# EstopperSchema.net
KiCad netlist of a schematic drawn in EAGLE
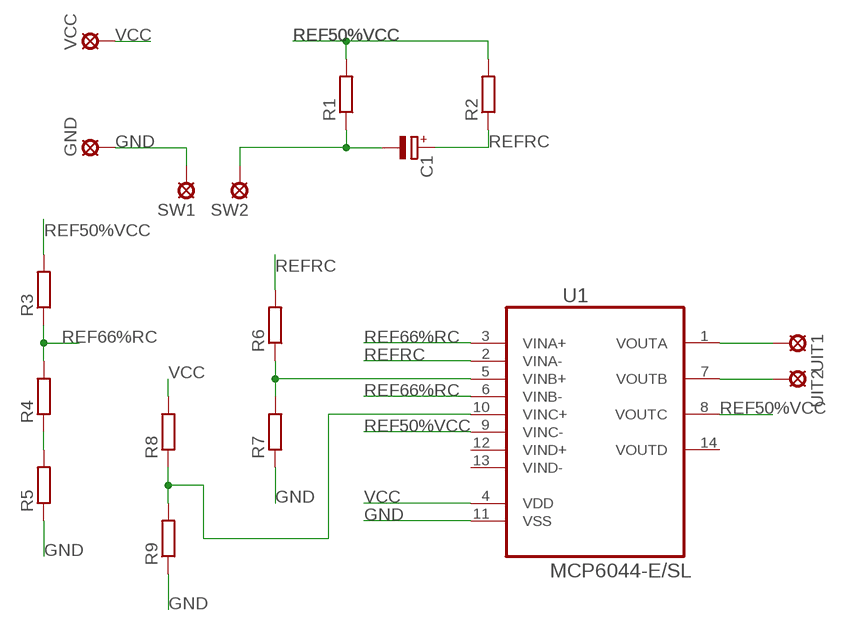
[diagram p0: schematic, sheet 1]

(export (version "E")
  (design (tool "Eeschema 10.0.6"))
  (components
    (comp (ref "C1")
      (value "CPOL-EU140CLH-0810")
      (footprint "eagle-import:140CLH-0810")
      (libsource (lib "eagle-import") (part "CPOL-EU140CLH-0810"))
    )
    (comp (ref "GND")
      (value "LSP11")
      (footprint "eagle-import:LSP11")
      (libsource (lib "eagle-import") (part "LSP11"))
    )
    (comp (ref "R1")
      (value "R-EU_M1206")
      (footprint "eagle-import:M1206")
      (libsource (lib "eagle-import") (part "R-EU_M1206"))
    )
    (comp (ref "R2")
      (value "R-EU_M1206")
      (footprint "eagle-import:M1206")
      (libsource (lib "eagle-import") (part "R-EU_M1206"))
    )
    (comp (ref "R3")
      (value "R-EU_M1206")
      (footprint "eagle-import:M1206")
      (libsource (lib "eagle-import") (part "R-EU_M1206"))
    )
    (comp (ref "R4")
      (value "R-EU_M1206")
      (footprint "eagle-import:M1206")
      (libsource (lib "eagle-import") (part "R-EU_M1206"))
    )
    (comp (ref "R5")
      (value "R-EU_M1206")
      (footprint "eagle-import:M1206")
      (libsource (lib "eagle-import") (part "R-EU_M1206"))
    )
    (comp (ref "R6")
      (value "R-EU_M1206")
      (footprint "eagle-import:M1206")
      (libsource (lib "eagle-import") (part "R-EU_M1206"))
    )
    (comp (ref "R7")
      (value "R-EU_M1206")
      (footprint "eagle-import:M1206")
      (libsource (lib "eagle-import") (part "R-EU_M1206"))
    )
    (comp (ref "R8")
      (value "R-EU_M1206")
      (footprint "eagle-import:M1206")
      (libsource (lib "eagle-import") (part "R-EU_M1206"))
    )
    (comp (ref "R9")
      (value "R-EU_M1206")
      (footprint "eagle-import:M1206")
      (libsource (lib "eagle-import") (part "R-EU_M1206"))
    )
    (comp (ref "SW1")
      (value "LSP11")
      (footprint "eagle-import:LSP11")
      (libsource (lib "eagle-import") (part "LSP11"))
    )
    (comp (ref "SW2")
      (value "LSP11")
      (footprint "eagle-import:LSP11")
      (libsource (lib "eagle-import") (part "LSP11"))
    )
    (comp (ref "U1")
      (value "MCP6044-E/SL")
      (footprint "eagle-import:SOIC127P600X175-14N")
      (libsource (lib "eagle-import") (part "MCP6044-E/SL"))
    )
    (comp (ref "UIT1")
      (value "LSP11")
      (footprint "eagle-import:LSP11")
      (libsource (lib "eagle-import") (part "LSP11"))
    )
    (comp (ref "UIT2")
      (value "LSP11")
      (footprint "eagle-import:LSP11")
      (libsource (lib "eagle-import") (part "LSP11"))
    )
    (comp (ref "VCC")
      (value "LSP11")
      (footprint "eagle-import:LSP11")
      (libsource (lib "eagle-import") (part "LSP11"))
    )
  )
  (nets
    (net (code "1") (name "/GND") (class "Default")
      (node (ref "GND") (pin "MP") (pinfunction "MP_MP") (pintype "passive"))
      (node (ref "R5") (pin "1") (pinfunction "1_1") (pintype "passive"))
      (node (ref "R7") (pin "1") (pinfunction "1_1") (pintype "passive"))
      (node (ref "R9") (pin "1") (pinfunction "1_1") (pintype "passive"))
      (node (ref "SW1") (pin "MP") (pinfunction "MP_MP") (pintype "passive"))
      (node (ref "U1") (pin "11") (pinfunction "VSS_11") (pintype "passive"))
    )
    (net (code "2") (name "/REF50%VCC") (class "Default")
      (node (ref "R1") (pin "2") (pinfunction "2_2") (pintype "passive"))
      (node (ref "R2") (pin "2") (pinfunction "2_2") (pintype "passive"))
      (node (ref "R3") (pin "2") (pinfunction "2_2") (pintype "passive"))
      (node (ref "U1") (pin "8") (pinfunction "VOUTC_8") (pintype "output"))
      (node (ref "U1") (pin "9") (pinfunction "VINC-_9") (pintype "input"))
    )
    (net (code "3") (name "/REF66%RC") (class "Default")
      (node (ref "R3") (pin "1") (pinfunction "1_1") (pintype "passive"))
      (node (ref "R4") (pin "2") (pinfunction "2_2") (pintype "passive"))
      (node (ref "U1") (pin "3") (pinfunction "VINA+_3") (pintype "input"))
      (node (ref "U1") (pin "6") (pinfunction "VINB-_6") (pintype "input"))
    )
    (net (code "4") (name "/REFRC") (class "Default")
      (node (ref "C1") (pin "+") (pinfunction "+_+") (pintype "passive"))
      (node (ref "R2") (pin "1") (pinfunction "1_1") (pintype "passive"))
      (node (ref "R6") (pin "2") (pinfunction "2_2") (pintype "passive"))
      (node (ref "U1") (pin "2") (pinfunction "VINA-_2") (pintype "input"))
    )
    (net (code "5") (name "/VCC") (class "Default")
      (node (ref "R8") (pin "2") (pinfunction "2_2") (pintype "passive"))
      (node (ref "U1") (pin "4") (pinfunction "VDD_4") (pintype "power_in"))
      (node (ref "VCC") (pin "MP") (pinfunction "MP_MP") (pintype "passive"))
    )
    (net (code "6") (name "Net-(C1-Pad-)") (class "Default")
      (node (ref "C1") (pin "-") (pinfunction "-_-") (pintype "passive"))
      (node (ref "R1") (pin "1") (pinfunction "1_1") (pintype "passive"))
      (node (ref "SW2") (pin "MP") (pinfunction "MP_MP") (pintype "passive"))
    )
    (net (code "7") (name "Net-(R4-Pad1)") (class "Default")
      (node (ref "R4") (pin "1") (pinfunction "1_1") (pintype "passive"))
      (node (ref "R5") (pin "2") (pinfunction "2_2") (pintype "passive"))
    )
    (net (code "8") (name "Net-(U1-VINB+)") (class "Default")
      (node (ref "R6") (pin "1") (pinfunction "1_1") (pintype "passive"))
      (node (ref "R7") (pin "2") (pinfunction "2_2") (pintype "passive"))
      (node (ref "U1") (pin "5") (pinfunction "VINB+_5") (pintype "input"))
    )
    (net (code "9") (name "Net-(U1-VINC+)") (class "Default")
      (node (ref "R8") (pin "1") (pinfunction "1_1") (pintype "passive"))
      (node (ref "R9") (pin "2") (pinfunction "2_2") (pintype "passive"))
      (node (ref "U1") (pin "10") (pinfunction "VINC+_10") (pintype "input"))
    )
    (net (code "10") (name "Net-(U1-VOUTA)") (class "Default")
      (node (ref "U1") (pin "1") (pinfunction "VOUTA_1") (pintype "output"))
      (node (ref "UIT1") (pin "MP") (pinfunction "MP_MP") (pintype "passive"))
    )
    (net (code "11") (name "Net-(U1-VOUTB)") (class "Default")
      (node (ref "U1") (pin "7") (pinfunction "VOUTB_7") (pintype "output"))
      (node (ref "UIT2") (pin "MP") (pinfunction "MP_MP") (pintype "passive"))
    )
    (net (code "12") (name "unconnected-(U1-VIND+-Pad12)") (class "Default")
      (node (ref "U1") (pin "12") (pinfunction "VIND+_12") (pintype "input"))
    )
    (net (code "13") (name "unconnected-(U1-VIND--Pad13)") (class "Default")
      (node (ref "U1") (pin "13") (pinfunction "VIND-_13") (pintype "input"))
    )
    (net (code "14") (name "unconnected-(U1-VOUTD-Pad14)") (class "Default")
      (node (ref "U1") (pin "14") (pinfunction "VOUTD_14") (pintype "output"))
    )
  )
)
